# vehicle_control.net
KiCad netlist of a schematic drawn in Altium Designer
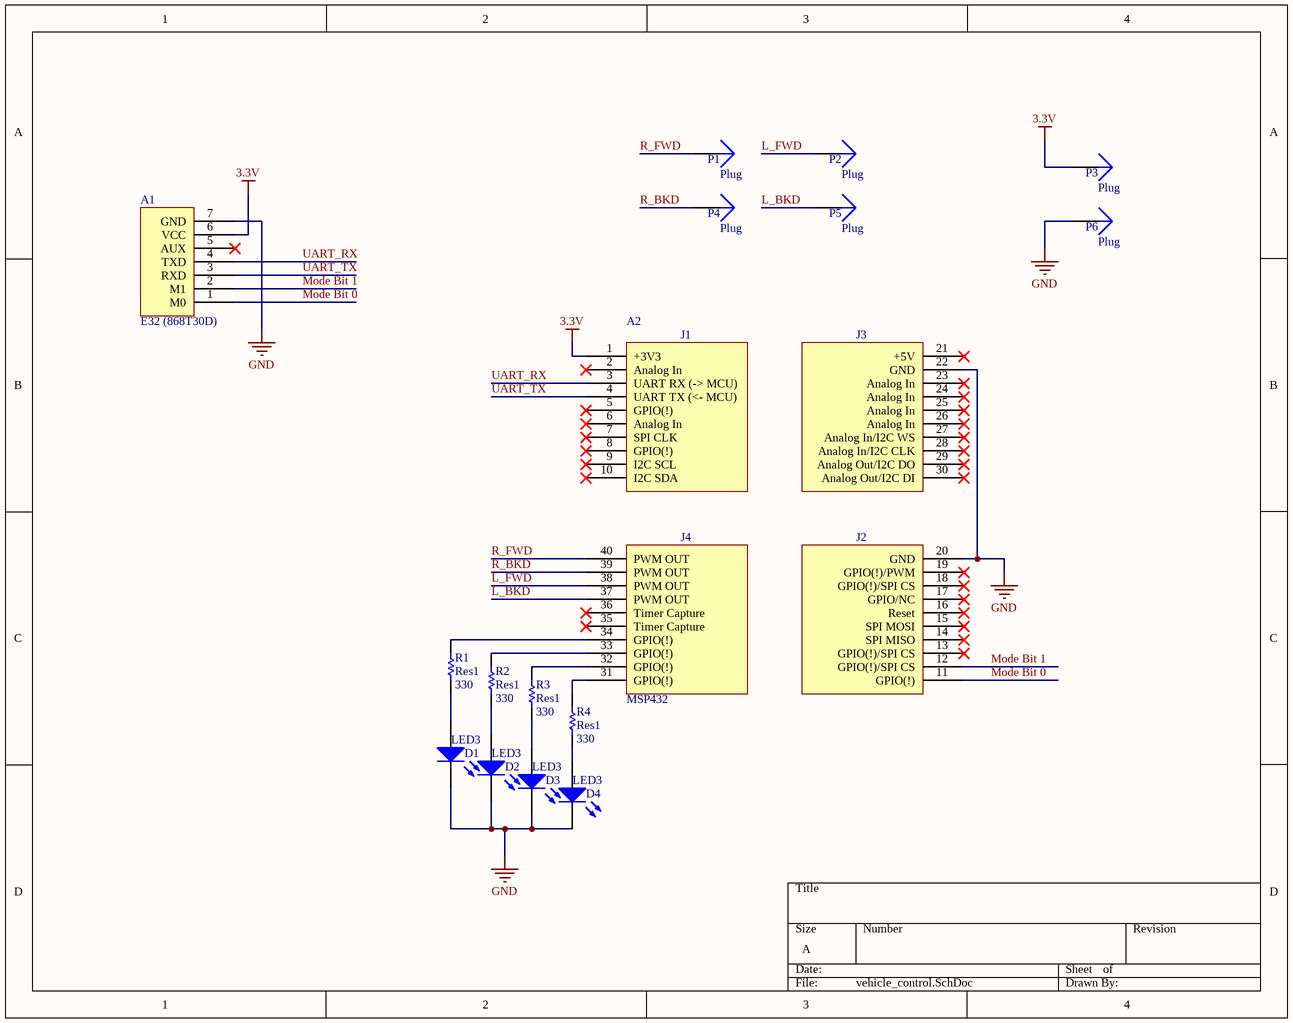
[diagram p0: vehicle_control.SchDoc]

(export (version "E")
  (design (tool "Eeschema 10.0.6"))
  (components
    (comp (ref "A1")
      (value "E32 (868T30D)")
      (footprint "HDR1X7")
      (libsource (lib "vehicle_control") (part "SX1276 E32"))
    )
    (comp (ref "A2")
      (value "MSP432")
      (footprint "MSP432")
      (description "MSP432 Dev Kit Launchpad")
      (libsource (lib "vehicle_control") (part "MSP432"))
    )
    (comp (ref "D1")
      (value "LED3")
      (footprint "Diode")
      (description "Typical BLUE SiC LED")
      (fields (field (name "PUBLISHER") "Altium Limited"))
      (libsource (lib "Miscellaneous Devices") (part "LED3"))
    )
    (comp (ref "D2")
      (value "LED3")
      (footprint "Diode")
      (description "Typical BLUE SiC LED")
      (fields (field (name "PUBLISHER") "Altium Limited"))
      (libsource (lib "Miscellaneous Devices") (part "LED3"))
    )
    (comp (ref "D3")
      (value "LED3")
      (footprint "Diode")
      (description "Typical BLUE SiC LED")
      (fields (field (name "PUBLISHER") "Altium Limited"))
      (libsource (lib "Miscellaneous Devices") (part "LED3"))
    )
    (comp (ref "D4")
      (value "LED3")
      (footprint "control_pcb_lib:Diode")
      (description "Typical BLUE SiC LED")
      (fields (field (name "PUBLISHER") "Altium Limited"))
      (libsource (lib "Miscellaneous Devices") (part "LED3"))
    )
    (comp (ref "P1")
      (value "Plug")
      (footprint "STANDOFF")
      (fields (field (name "PUBLISHER") "Altium Limited"))
      (libsource (lib "Miscellaneous Connectors") (part "Plug"))
    )
    (comp (ref "P2")
      (value "Plug")
      (footprint "STANDOFF")
      (fields (field (name "PUBLISHER") "Altium Limited"))
      (libsource (lib "Miscellaneous Connectors") (part "Plug"))
    )
    (comp (ref "P3")
      (value "Plug")
      (footprint "STANDOFF")
      (fields (field (name "PUBLISHER") "Altium Limited"))
      (libsource (lib "Miscellaneous Connectors") (part "Plug"))
    )
    (comp (ref "P4")
      (value "Plug")
      (footprint "STANDOFF")
      (fields (field (name "PUBLISHER") "Altium Limited"))
      (libsource (lib "Miscellaneous Connectors") (part "Plug"))
    )
    (comp (ref "P5")
      (value "Plug")
      (footprint "STANDOFF")
      (fields (field (name "PUBLISHER") "Altium Limited"))
      (libsource (lib "Miscellaneous Connectors") (part "Plug"))
    )
    (comp (ref "P6")
      (value "Plug")
      (footprint "STANDOFF")
      (fields (field (name "PUBLISHER") "Altium Limited"))
      (libsource (lib "Miscellaneous Connectors") (part "Plug"))
    )
    (comp (ref "R1")
      (value "Res1")
      (footprint "AXIAL-0.3")
      (description "Resistor")
      (fields (field (name "ALTIUM_VALUE") "330") (field (name "PUBLISHER") "Altium Limited"))
      (libsource (lib "Miscellaneous Devices") (part "Res1"))
    )
    (comp (ref "R2")
      (value "Res1")
      (footprint "AXIAL-0.3")
      (description "Resistor")
      (fields (field (name "ALTIUM_VALUE") "330") (field (name "PUBLISHER") "Altium Limited"))
      (libsource (lib "Miscellaneous Devices") (part "Res1"))
    )
    (comp (ref "R3")
      (value "Res1")
      (footprint "AXIAL-0.3")
      (description "Resistor")
      (fields (field (name "ALTIUM_VALUE") "330") (field (name "PUBLISHER") "Altium Limited"))
      (libsource (lib "Miscellaneous Devices") (part "Res1"))
    )
    (comp (ref "R4")
      (value "Res1")
      (footprint "AXIAL-0.3")
      (description "Resistor")
      (fields (field (name "ALTIUM_VALUE") "330") (field (name "PUBLISHER") "Altium Limited"))
      (libsource (lib "Miscellaneous Devices") (part "Res1"))
    )
  )
  (nets
    (net (code "1") (name "/L_BKD") (class "Default")
      (node (ref "A2") (pin "37") (pinfunction "PWM_OUT_37") (pintype "passive"))
      (node (ref "P5") (pin "1") (pinfunction "1_1") (pintype "passive"))
    )
    (net (code "2") (name "/L_FWD") (class "Default")
      (node (ref "A2") (pin "38") (pinfunction "PWM_OUT_38") (pintype "passive"))
      (node (ref "P2") (pin "1") (pinfunction "1_1") (pintype "passive"))
    )
    (net (code "3") (name "/Mode Bit 0") (class "Default")
      (node (ref "A1") (pin "1") (pinfunction "M0_1") (pintype "passive"))
      (node (ref "A2") (pin "11") (pinfunction "GPIO(!)_11") (pintype "passive"))
    )
    (net (code "4") (name "/Mode Bit 1") (class "Default")
      (node (ref "A1") (pin "2") (pinfunction "M1_2") (pintype "passive"))
      (node (ref "A2") (pin "12") (pinfunction "GPIO(!)/SPI_CS_12") (pintype "passive"))
    )
    (net (code "5") (name "/R_BKD") (class "Default")
      (node (ref "A2") (pin "39") (pinfunction "PWM_OUT_39") (pintype "passive"))
      (node (ref "P4") (pin "1") (pinfunction "1_1") (pintype "passive"))
    )
    (net (code "6") (name "/R_FWD") (class "Default")
      (node (ref "A2") (pin "40") (pinfunction "PWM_OUT_40") (pintype "passive"))
      (node (ref "P1") (pin "1") (pinfunction "1_1") (pintype "passive"))
    )
    (net (code "7") (name "/UART_RX") (class "Default")
      (node (ref "A1") (pin "4") (pinfunction "TXD_4") (pintype "passive"))
      (node (ref "A2") (pin "3") (pinfunction "UART_RX_(->_MCU)_3") (pintype "passive"))
    )
    (net (code "8") (name "/UART_TX") (class "Default")
      (node (ref "A1") (pin "3") (pinfunction "RXD_3") (pintype "passive"))
      (node (ref "A2") (pin "4") (pinfunction "UART_TX_(<-_MCU)_4") (pintype "passive"))
    )
    (net (code "9") (name "3.3V") (class "Default")
      (node (ref "A1") (pin "6") (pinfunction "VCC_6") (pintype "passive"))
      (node (ref "A2") (pin "1") (pinfunction "+3V3_1") (pintype "power_in"))
      (node (ref "P3") (pin "1") (pinfunction "1_1") (pintype "passive"))
    )
    (net (code "10") (name "GND") (class "Default")
      (node (ref "A1") (pin "7") (pinfunction "GND_7") (pintype "passive"))
      (node (ref "A2") (pin "20") (pinfunction "GND_20") (pintype "passive"))
      (node (ref "A2") (pin "22") (pinfunction "GND_22") (pintype "passive"))
      (node (ref "D1") (pin "2") (pinfunction "K_2") (pintype "passive"))
      (node (ref "D2") (pin "2") (pinfunction "K_2") (pintype "passive"))
      (node (ref "D3") (pin "2") (pinfunction "K_2") (pintype "passive"))
      (node (ref "D4") (pin "2") (pinfunction "K_2") (pintype "passive"))
      (node (ref "P6") (pin "1") (pinfunction "1_1") (pintype "passive"))
    )
    (net (code "11") (name "Net-(A2-GPIO(!)-Pad31)") (class "Default")
      (node (ref "A2") (pin "31") (pinfunction "GPIO(!)_31") (pintype "passive"))
      (node (ref "R4") (pin "1") (pinfunction "1_1") (pintype "passive"))
    )
    (net (code "12") (name "Net-(A2-GPIO(!)-Pad32)") (class "Default")
      (node (ref "A2") (pin "32") (pinfunction "GPIO(!)_32") (pintype "passive"))
      (node (ref "R3") (pin "1") (pinfunction "1_1") (pintype "passive"))
    )
    (net (code "13") (name "Net-(A2-GPIO(!)-Pad33)") (class "Default")
      (node (ref "A2") (pin "33") (pinfunction "GPIO(!)_33") (pintype "passive"))
      (node (ref "R2") (pin "1") (pinfunction "1_1") (pintype "passive"))
    )
    (net (code "14") (name "Net-(A2-GPIO(!)-Pad34)") (class "Default")
      (node (ref "A2") (pin "34") (pinfunction "GPIO(!)_34") (pintype "passive"))
      (node (ref "R1") (pin "1") (pinfunction "1_1") (pintype "passive"))
    )
    (net (code "15") (name "Net-(D1-A)") (class "Default")
      (node (ref "D1") (pin "1") (pinfunction "A_1") (pintype "passive"))
      (node (ref "R1") (pin "2") (pinfunction "2_2") (pintype "passive"))
    )
    (net (code "16") (name "Net-(D2-A)") (class "Default")
      (node (ref "D2") (pin "1") (pinfunction "A_1") (pintype "passive"))
      (node (ref "R2") (pin "2") (pinfunction "2_2") (pintype "passive"))
    )
    (net (code "17") (name "Net-(D3-A)") (class "Default")
      (node (ref "D3") (pin "1") (pinfunction "A_1") (pintype "passive"))
      (node (ref "R3") (pin "2") (pinfunction "2_2") (pintype "passive"))
    )
    (net (code "18") (name "Net-(D4-A)") (class "Default")
      (node (ref "D4") (pin "1") (pinfunction "A_1") (pintype "passive"))
      (node (ref "R4") (pin "2") (pinfunction "2_2") (pintype "passive"))
    )
    (net (code "19") (name "unconnected-(A1-AUX-Pad5)") (class "Default")
      (node (ref "A1") (pin "5") (pinfunction "AUX_5") (pintype "passive+no_connect"))
    )
    (net (code "20") (name "unconnected-(A2-+5V-Pad21)") (class "Default")
      (node (ref "A2") (pin "21") (pinfunction "+5V_21") (pintype "passive+no_connect"))
    )
    (net (code "21") (name "unconnected-(A2-Analog_In-Pad2)") (class "Default")
      (node (ref "A2") (pin "2") (pinfunction "Analog_In_2") (pintype "passive+no_connect"))
    )
    (net (code "22") (name "unconnected-(A2-Analog_In-Pad6)") (class "Default")
      (node (ref "A2") (pin "6") (pinfunction "Analog_In_6") (pintype "passive+no_connect"))
    )
    (net (code "23") (name "unconnected-(A2-Analog_In-Pad23)") (class "Default")
      (node (ref "A2") (pin "23") (pinfunction "Analog_In_23") (pintype "passive+no_connect"))
    )
    (net (code "24") (name "unconnected-(A2-Analog_In-Pad24)") (class "Default")
      (node (ref "A2") (pin "24") (pinfunction "Analog_In_24") (pintype "passive+no_connect"))
    )
    (net (code "25") (name "unconnected-(A2-Analog_In-Pad25)") (class "Default")
      (node (ref "A2") (pin "25") (pinfunction "Analog_In_25") (pintype "passive+no_connect"))
    )
    (net (code "26") (name "unconnected-(A2-Analog_In-Pad26)") (class "Default")
      (node (ref "A2") (pin "26") (pinfunction "Analog_In_26") (pintype "passive+no_connect"))
    )
    (net (code "27") (name "unconnected-(A2-Analog_In{slash}I2C_CLK-Pad28)") (class "Default")
      (node (ref "A2") (pin "28") (pinfunction "Analog_In/I2C_CLK_28") (pintype "passive+no_connect"))
    )
    (net (code "28") (name "unconnected-(A2-Analog_In{slash}I2C_WS-Pad27)") (class "Default")
      (node (ref "A2") (pin "27") (pinfunction "Analog_In/I2C_WS_27") (pintype "passive+no_connect"))
    )
    (net (code "29") (name "unconnected-(A2-Analog_Out{slash}I2C_DI-Pad30)") (class "Default")
      (node (ref "A2") (pin "30") (pinfunction "Analog_Out/I2C_DI_30") (pintype "passive+no_connect"))
    )
    (net (code "30") (name "unconnected-(A2-Analog_Out{slash}I2C_DO-Pad29)") (class "Default")
      (node (ref "A2") (pin "29") (pinfunction "Analog_Out/I2C_DO_29") (pintype "passive+no_connect"))
    )
    (net (code "31") (name "unconnected-(A2-GPIO(!)-Pad5)") (class "Default")
      (node (ref "A2") (pin "5") (pinfunction "GPIO(!)_5") (pintype "passive+no_connect"))
    )
    (net (code "32") (name "unconnected-(A2-GPIO(!)-Pad8)") (class "Default")
      (node (ref "A2") (pin "8") (pinfunction "GPIO(!)_8") (pintype "passive+no_connect"))
    )
    (net (code "33") (name "unconnected-(A2-GPIO(!){slash}PWM-Pad19)") (class "Default")
      (node (ref "A2") (pin "19") (pinfunction "GPIO(!)/PWM_19") (pintype "passive+no_connect"))
    )
    (net (code "34") (name "unconnected-(A2-GPIO(!){slash}SPI_CS-Pad13)") (class "Default")
      (node (ref "A2") (pin "13") (pinfunction "GPIO(!)/SPI_CS_13") (pintype "passive+no_connect"))
    )
    (net (code "35") (name "unconnected-(A2-GPIO(!){slash}SPI_CS-Pad18)") (class "Default")
      (node (ref "A2") (pin "18") (pinfunction "GPIO(!)/SPI_CS_18") (pintype "passive+no_connect"))
    )
    (net (code "36") (name "unconnected-(A2-GPIO{slash}NC-Pad17)") (class "Default")
      (node (ref "A2") (pin "17") (pinfunction "GPIO/NC_17") (pintype "passive+no_connect"))
    )
    (net (code "37") (name "unconnected-(A2-I2C_SCL-Pad9)") (class "Default")
      (node (ref "A2") (pin "9") (pinfunction "I2C_SCL_9") (pintype "passive+no_connect"))
    )
    (net (code "38") (name "unconnected-(A2-I2C_SDA-Pad10)") (class "Default")
      (node (ref "A2") (pin "10") (pinfunction "I2C_SDA_10") (pintype "passive+no_connect"))
    )
    (net (code "39") (name "unconnected-(A2-Reset-Pad16)") (class "Default")
      (node (ref "A2") (pin "16") (pinfunction "Reset_16") (pintype "passive+no_connect"))
    )
    (net (code "40") (name "unconnected-(A2-SPI_CLK-Pad7)") (class "Default")
      (node (ref "A2") (pin "7") (pinfunction "SPI_CLK_7") (pintype "passive+no_connect"))
    )
    (net (code "41") (name "unconnected-(A2-SPI_MISO-Pad14)") (class "Default")
      (node (ref "A2") (pin "14") (pinfunction "SPI_MISO_14") (pintype "passive+no_connect"))
    )
    (net (code "42") (name "unconnected-(A2-SPI_MOSI-Pad15)") (class "Default")
      (node (ref "A2") (pin "15") (pinfunction "SPI_MOSI_15") (pintype "passive+no_connect"))
    )
    (net (code "43") (name "unconnected-(A2-Timer_Capture-Pad35)") (class "Default")
      (node (ref "A2") (pin "35") (pinfunction "Timer_Capture_35") (pintype "passive+no_connect"))
    )
    (net (code "44") (name "unconnected-(A2-Timer_Capture-Pad36)") (class "Default")
      (node (ref "A2") (pin "36") (pinfunction "Timer_Capture_36") (pintype "passive+no_connect"))
    )
  )
)
